# 2002_PIC32.net
KiCad netlist of a schematic drawn in Altium Designer
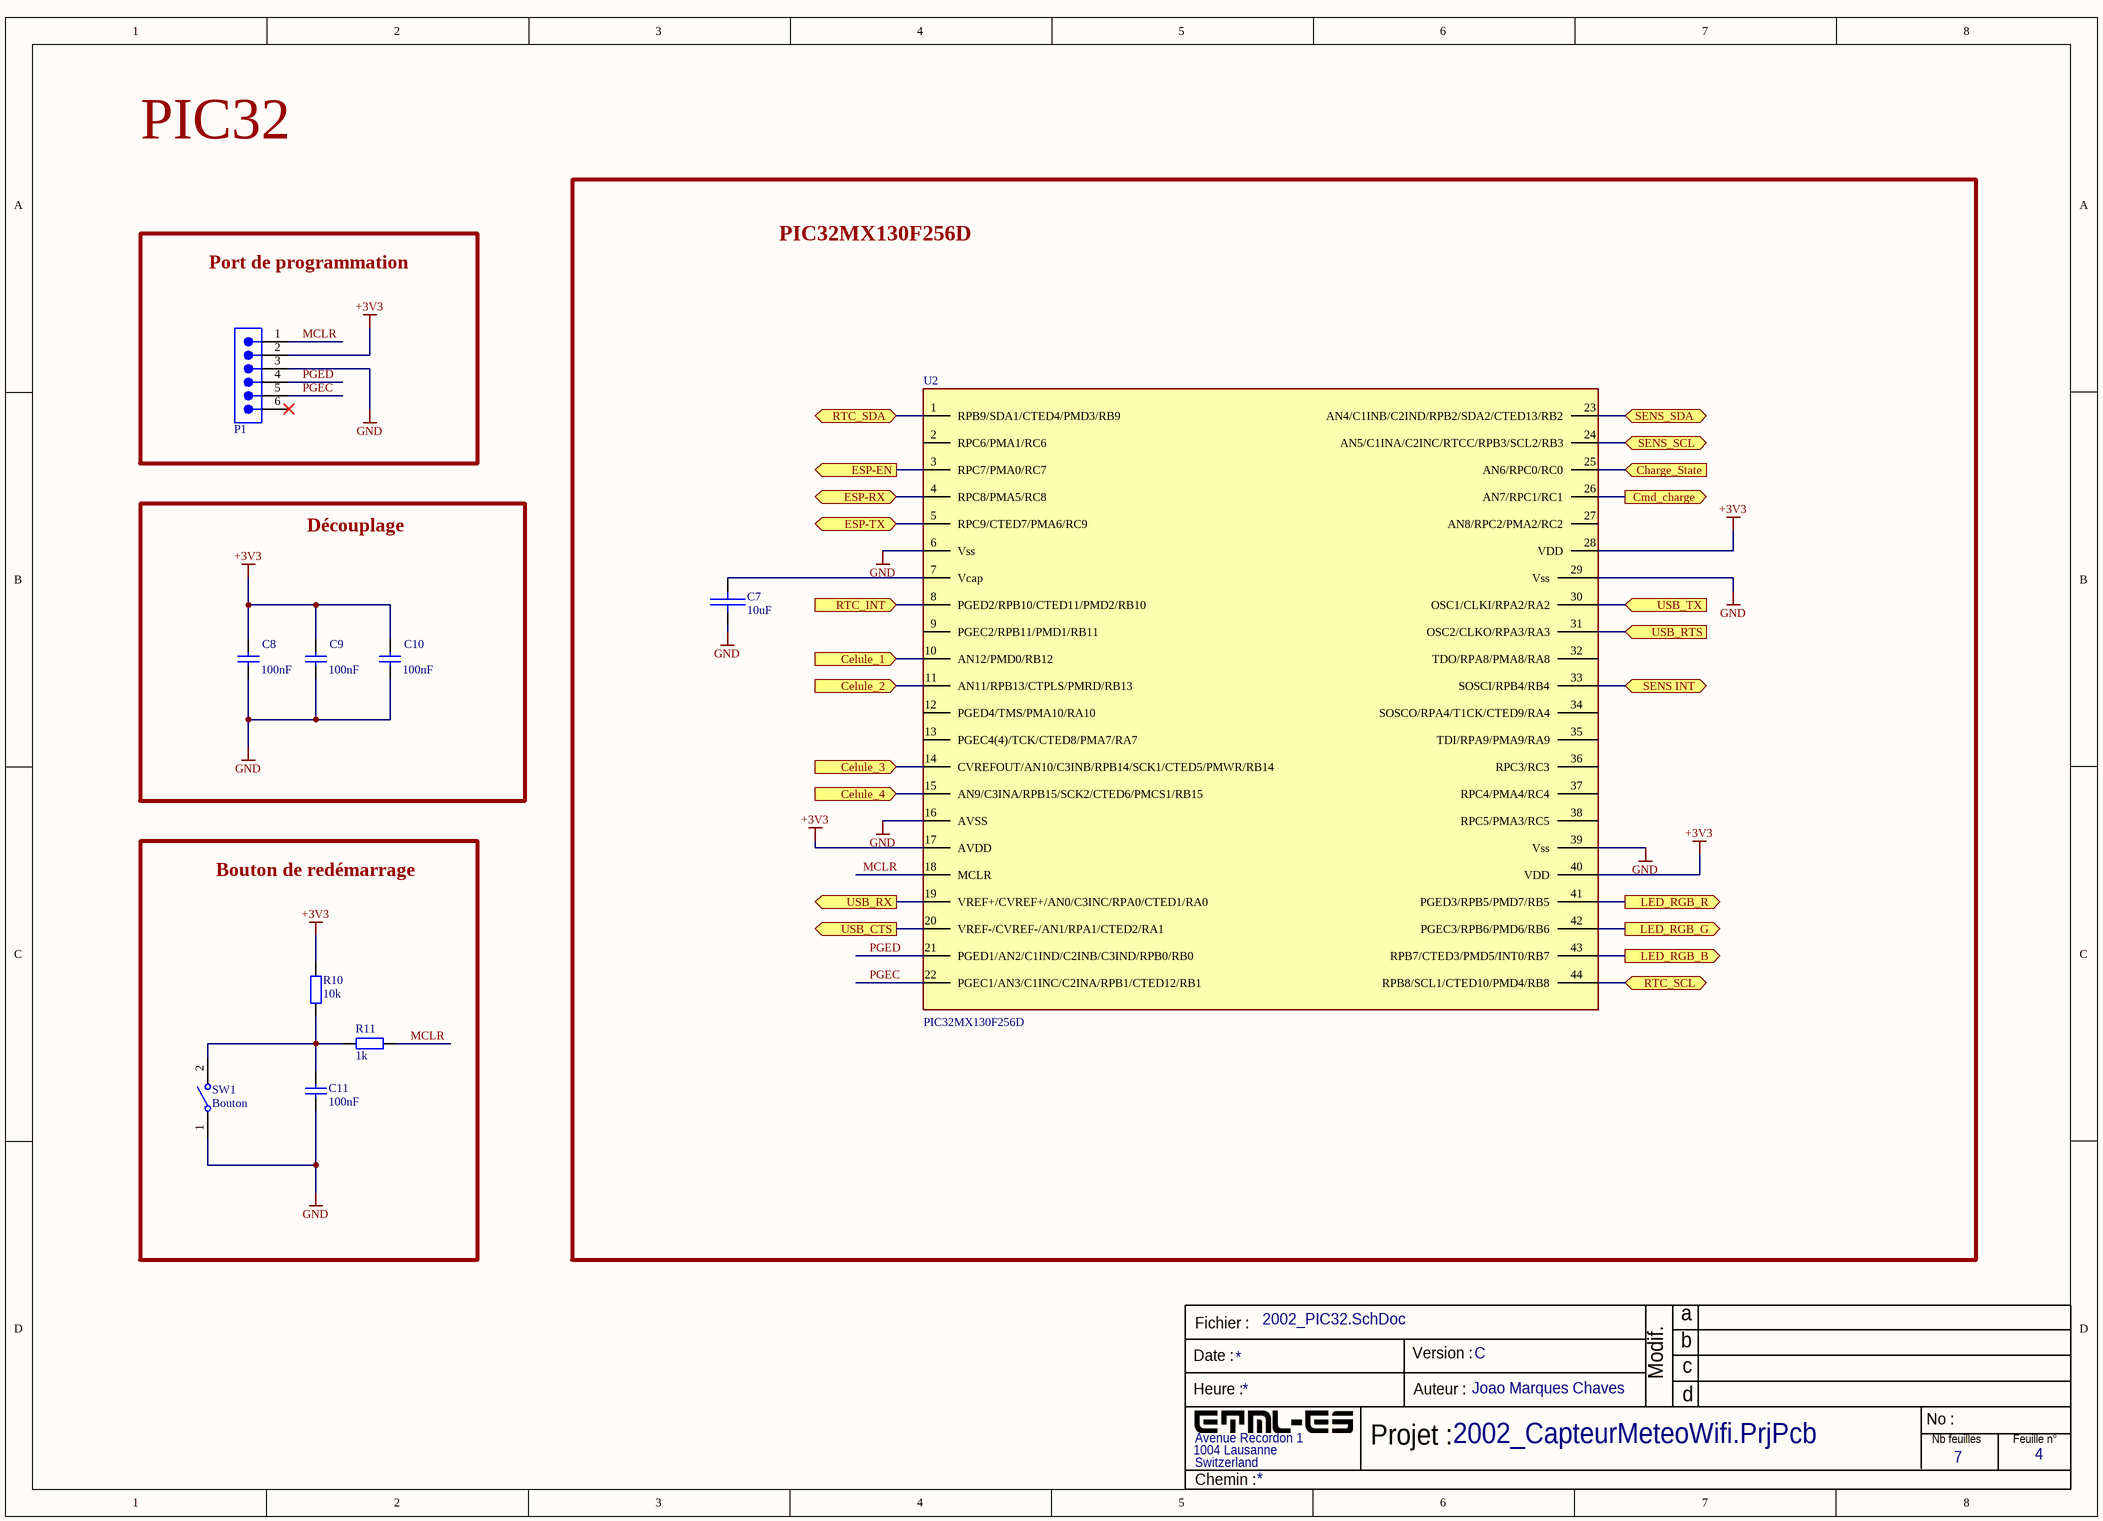
[diagram p0: 2002_PIC32.SchDoc]

(export (version "E")
  (design (tool "Eeschema 10.0.6"))
  (components
    (comp (ref "C7")
      (value "10uF")
      (footprint "0805")
      (description "0805 Condensator")
      (libsource (lib "2002_CapteurMeteoWifi") (part "Condensator"))
    )
    (comp (ref "C8")
      (value "100nF")
      (footprint "0805")
      (description "Capacitor smd")
      (fields
        (field (name "MANUFACTURER PART NUMBER") "885012207016")
        (field (name "MANUFACTURER") "Wurth Elektronik")
        (field (name "CAPACITANCE") "100nF")
      )
      (libsource (lib "WCAP-CSGP") (part "885012207016"))
    )
    (comp (ref "C9")
      (value "100nF")
      (footprint "0805")
      (description "Capacitor smd")
      (fields
        (field (name "MANUFACTURER PART NUMBER") "885012207016")
        (field (name "MANUFACTURER") "Wurth Elektronik")
        (field (name "CAPACITANCE") "100nF")
      )
      (libsource (lib "WCAP-CSGP") (part "885012207016"))
    )
    (comp (ref "C10")
      (value "100nF")
      (footprint "0805")
      (description "Capacitor smd")
      (fields
        (field (name "MANUFACTURER PART NUMBER") "885012207016")
        (field (name "MANUFACTURER") "Wurth Elektronik")
        (field (name "CAPACITANCE") "100nF")
      )
      (libsource (lib "WCAP-CSGP") (part "885012207016"))
    )
    (comp (ref "C11")
      (value "100nF")
      (footprint "0805")
      (description "Capacitor smd")
      (fields
        (field (name "MANUFACTURER PART NUMBER") "885012207016")
        (field (name "MANUFACTURER") "Wurth Elektronik")
        (field (name "CAPACITANCE") "100nF")
      )
      (libsource (lib "WCAP-CSGP") (part "885012207016"))
    )
    (comp (ref "P1")
      (value "6 Pin header")
      (footprint "conecteur 1x6")
      (description "WR-PHD Pin Header, THT, Vertical, pitch 2.54mm, 1 Row, 6P")
      (fields
        (field (name "MANUFACTURER PART NUMBER") "61300611121")
        (field (name "MANUFACTURER") "Wurth Elektronik")
      )
      (libsource (lib "WR-PHD") (part "61300611121"))
    )
    (comp (ref "R10")
      (value "10k")
      (footprint "0805")
      (description "SMD Resistor")
      (fields (field (name "RESISTANCE") "10k"))
      (libsource (lib "2312-MS-0805") (part "RES-0805"))
    )
    (comp (ref "R11")
      (value "1k")
      (footprint "0805")
      (description "SMD Resistor")
      (fields (field (name "RESISTANCE") "1k"))
      (libsource (lib "2312-MS-0805") (part "RES-0805"))
    )
    (comp (ref "SW1")
      (value "Bouton")
      (footprint "Switch")
      (description "Tactile Switches WS-TASV Tact Switch")
      (fields
        (field (name "MANUFACTURER PART NUMBER") "434121050836")
        (field (name "MANUFACTURER") "Wurth Elektronik")
      )
      (libsource (lib "WS-TASV") (part "434121050836"))
    )
    (comp (ref "U2")
      (value "PIC32MX130F256D")
      (footprint "PIC32MX130F256D-I/PT")
      (description "Integrated Circuit")
      (fields
        (field (name "MANUFACTURER_PART_NUMBER") "PIC32MX130F256D-50I/PT")
        (field (name "MOUSER PART NUMBER") "579-MX130F256D50IPT")
      )
      (libsource (lib "2002_CapteurMeteoWifi") (part "PIC32MX130F256B-I_SS"))
    )
  )
  (nets
    (net (code "1") (name "+3V3") (class "Default")
      (node (ref "C10") (pin "2") (pinfunction "2_2") (pintype "passive"))
      (node (ref "C8") (pin "2") (pinfunction "2_2") (pintype "passive"))
      (node (ref "C9") (pin "2") (pinfunction "2_2") (pintype "passive"))
      (node (ref "P1") (pin "2") (pinfunction "2_2") (pintype "passive"))
      (node (ref "R10") (pin "1") (pinfunction "1_1") (pintype "passive"))
      (node (ref "U2") (pin "17") (pinfunction "AVDD_17") (pintype "passive"))
      (node (ref "U2") (pin "28") (pinfunction "VDD_28") (pintype "passive"))
      (node (ref "U2") (pin "40") (pinfunction "VDD_40") (pintype "passive"))
    )
    (net (code "2") (name "/Celule_1") (class "Default")
      (node (ref "U2") (pin "10") (pinfunction "AN12/PMD0/RB12_10") (pintype "passive"))
    )
    (net (code "3") (name "/Celule_2") (class "Default")
      (node (ref "U2") (pin "11") (pinfunction "AN11/RPB13/CTPLS/PMRD/RB13_11") (pintype "passive"))
    )
    (net (code "4") (name "/Celule_3") (class "Default")
      (node (ref "U2") (pin "14") (pinfunction "CVREFOUT/AN10/C3INB/RPB14/SCK1/CTED5/PMWR/RB14_14") (pintype "passive"))
    )
    (net (code "5") (name "/Celule_4") (class "Default")
      (node (ref "U2") (pin "15") (pinfunction "AN9/C3INA/RPB15/SCK2/CTED6/PMCS1/RB15_15") (pintype "passive"))
    )
    (net (code "6") (name "/Charge_State") (class "Default")
      (node (ref "U2") (pin "25") (pinfunction "AN6/RPC0/RC0_25") (pintype "passive"))
    )
    (net (code "7") (name "/Cmd_charge") (class "Default")
      (node (ref "U2") (pin "26") (pinfunction "AN7/RPC1/RC1_26") (pintype "passive"))
    )
    (net (code "8") (name "/ESP-EN") (class "Default")
      (node (ref "U2") (pin "3") (pinfunction "RPC7/PMA0/RC7_3") (pintype "passive"))
    )
    (net (code "9") (name "/ESP-RX") (class "Default")
      (node (ref "U2") (pin "4") (pinfunction "RPC8/PMA5/RC8_4") (pintype "passive"))
    )
    (net (code "10") (name "/ESP-TX") (class "Default")
      (node (ref "U2") (pin "5") (pinfunction "RPC9/CTED7/PMA6/RC9_5") (pintype "passive"))
    )
    (net (code "11") (name "/LED_RGB_B") (class "Default")
      (node (ref "U2") (pin "43") (pinfunction "RPB7/CTED3/PMD5/INT0/RB7_43") (pintype "passive"))
    )
    (net (code "12") (name "/LED_RGB_G") (class "Default")
      (node (ref "U2") (pin "42") (pinfunction "PGEC3/RPB6/PMD6/RB6_42") (pintype "passive"))
    )
    (net (code "13") (name "/LED_RGB_R") (class "Default")
      (node (ref "U2") (pin "41") (pinfunction "PGED3/RPB5/PMD7/RB5_41") (pintype "passive"))
    )
    (net (code "14") (name "/MCLR") (class "Default")
      (node (ref "P1") (pin "1") (pinfunction "1_1") (pintype "passive"))
      (node (ref "R11") (pin "2") (pinfunction "2_2") (pintype "passive"))
      (node (ref "U2") (pin "18") (pinfunction "MCLR_18") (pintype "passive"))
    )
    (net (code "15") (name "/PGEC") (class "Default")
      (node (ref "P1") (pin "5") (pinfunction "5_5") (pintype "passive"))
      (node (ref "U2") (pin "22") (pinfunction "PGEC1/AN3/C1INC/C2INA/RPB1/CTED12/RB1_22") (pintype "passive"))
    )
    (net (code "16") (name "/PGED") (class "Default")
      (node (ref "P1") (pin "4") (pinfunction "4_4") (pintype "passive"))
      (node (ref "U2") (pin "21") (pinfunction "PGED1/AN2/C1IND/C2INB/C3IND/RPB0/RB0_21") (pintype "passive"))
    )
    (net (code "17") (name "/RTC_INT") (class "Default")
      (node (ref "U2") (pin "8") (pinfunction "PGED2/RPB10/CTED11/PMD2/RB10_8") (pintype "passive"))
    )
    (net (code "18") (name "/RTC_SCL") (class "Default")
      (node (ref "U2") (pin "44") (pinfunction "RPB8/SCL1/CTED10/PMD4/RB8_44") (pintype "passive"))
    )
    (net (code "19") (name "/RTC_SDA") (class "Default")
      (node (ref "U2") (pin "1") (pinfunction "RPB9/SDA1/CTED4/PMD3/RB9_1") (pintype "passive"))
    )
    (net (code "20") (name "/SENS INT") (class "Default")
      (node (ref "U2") (pin "33") (pinfunction "SOSCI/RPB4/RB4_33") (pintype "passive"))
    )
    (net (code "21") (name "/SENS_SCL") (class "Default")
      (node (ref "U2") (pin "24") (pinfunction "AN5/C1INA/C2INC/RTCC/RPB3/SCL2/RB3_24") (pintype "passive"))
    )
    (net (code "22") (name "/SENS_SDA") (class "Default")
      (node (ref "U2") (pin "23") (pinfunction "AN4/C1INB/C2IND/RPB2/SDA2/CTED13/RB2_23") (pintype "passive"))
    )
    (net (code "23") (name "/USB_CTS") (class "Default")
      (node (ref "U2") (pin "20") (pinfunction "VREF-/CVREF-/AN1/RPA1/CTED2/RA1_20") (pintype "passive"))
    )
    (net (code "24") (name "/USB_RTS") (class "Default")
      (node (ref "U2") (pin "31") (pinfunction "OSC2/CLKO/RPA3/RA3_31") (pintype "passive"))
    )
    (net (code "25") (name "/USB_RX") (class "Default")
      (node (ref "U2") (pin "19") (pinfunction "VREF+/CVREF+/AN0/C3INC/RPA0/CTED1/RA0_19") (pintype "passive"))
    )
    (net (code "26") (name "/USB_TX") (class "Default")
      (node (ref "U2") (pin "30") (pinfunction "OSC1/CLKI/RPA2/RA2_30") (pintype "passive"))
    )
    (net (code "27") (name "GND") (class "Default")
      (node (ref "C10") (pin "1") (pinfunction "1_1") (pintype "passive"))
      (node (ref "C11") (pin "2") (pinfunction "2_2") (pintype "passive"))
      (node (ref "C7") (pin "2") (pinfunction "2_2") (pintype "passive"))
      (node (ref "C8") (pin "1") (pinfunction "1_1") (pintype "passive"))
      (node (ref "C9") (pin "1") (pinfunction "1_1") (pintype "passive"))
      (node (ref "P1") (pin "3") (pinfunction "3_3") (pintype "passive"))
      (node (ref "SW1") (pin "1") (pinfunction "1_1") (pintype "passive"))
      (node (ref "U2") (pin "16") (pinfunction "AVSS_16") (pintype "passive"))
      (node (ref "U2") (pin "29") (pinfunction "Vss_29") (pintype "passive"))
      (node (ref "U2") (pin "39") (pinfunction "Vss_39") (pintype "passive"))
      (node (ref "U2") (pin "6") (pinfunction "Vss_6") (pintype "passive"))
    )
    (net (code "28") (name "Net-(C11-Pad1)") (class "Default")
      (node (ref "C11") (pin "1") (pinfunction "1_1") (pintype "passive"))
      (node (ref "R10") (pin "2") (pinfunction "2_2") (pintype "passive"))
      (node (ref "R11") (pin "1") (pinfunction "1_1") (pintype "passive"))
      (node (ref "SW1") (pin "2") (pinfunction "2_2") (pintype "passive"))
    )
    (net (code "29") (name "Net-(U2-Vcap)") (class "Default")
      (node (ref "C7") (pin "1") (pinfunction "1_1") (pintype "passive"))
      (node (ref "U2") (pin "7") (pinfunction "Vcap_7") (pintype "passive"))
    )
    (net (code "30") (name "unconnected-(P1-Pad6)") (class "Default")
      (node (ref "P1") (pin "6") (pinfunction "6_6") (pintype "passive+no_connect"))
    )
    (net (code "31") (name "unconnected-(U2-AN8{slash}RPC2{slash}PMA2{slash}RC2-Pad27)") (class "Default")
      (node (ref "U2") (pin "27") (pinfunction "AN8/RPC2/PMA2/RC2_27") (pintype "passive"))
    )
    (net (code "32") (name "unconnected-(U2-PGEC2{slash}RPB11{slash}PMD1{slash}RB11-Pad9)") (class "Default")
      (node (ref "U2") (pin "9") (pinfunction "PGEC2/RPB11/PMD1/RB11_9") (pintype "passive"))
    )
    (net (code "33") (name "unconnected-(U2-PGEC4(4){slash}TCK{slash}CTED8{slash}PMA7{slash}RA7-Pad13)") (class "Default")
      (node (ref "U2") (pin "13") (pinfunction "PGEC4(4)/TCK/CTED8/PMA7/RA7_13") (pintype "passive"))
    )
    (net (code "34") (name "unconnected-(U2-PGED4{slash}TMS{slash}PMA10{slash}RA10-Pad12)") (class "Default")
      (node (ref "U2") (pin "12") (pinfunction "PGED4/TMS/PMA10/RA10_12") (pintype "passive"))
    )
    (net (code "35") (name "unconnected-(U2-RPC3{slash}RC3-Pad36)") (class "Default")
      (node (ref "U2") (pin "36") (pinfunction "RPC3/RC3_36") (pintype "passive"))
    )
    (net (code "36") (name "unconnected-(U2-RPC4{slash}PMA4{slash}RC4-Pad37)") (class "Default")
      (node (ref "U2") (pin "37") (pinfunction "RPC4/PMA4/RC4_37") (pintype "passive"))
    )
    (net (code "37") (name "unconnected-(U2-RPC5{slash}PMA3{slash}RC5-Pad38)") (class "Default")
      (node (ref "U2") (pin "38") (pinfunction "RPC5/PMA3/RC5_38") (pintype "passive"))
    )
    (net (code "38") (name "unconnected-(U2-RPC6{slash}PMA1{slash}RC6-Pad2)") (class "Default")
      (node (ref "U2") (pin "2") (pinfunction "RPC6/PMA1/RC6_2") (pintype "passive"))
    )
    (net (code "39") (name "unconnected-(U2-SOSCO{slash}RPA4{slash}T1CK{slash}CTED9{slash}RA4-Pad34)") (class "Default")
      (node (ref "U2") (pin "34") (pinfunction "SOSCO/RPA4/T1CK/CTED9/RA4_34") (pintype "passive"))
    )
    (net (code "40") (name "unconnected-(U2-TDI{slash}RPA9{slash}PMA9{slash}RA9-Pad35)") (class "Default")
      (node (ref "U2") (pin "35") (pinfunction "TDI/RPA9/PMA9/RA9_35") (pintype "passive"))
    )
    (net (code "41") (name "unconnected-(U2-TDO{slash}RPA8{slash}PMA8{slash}RA8-Pad32)") (class "Default")
      (node (ref "U2") (pin "32") (pinfunction "TDO/RPA8/PMA8/RA8_32") (pintype "passive"))
    )
  )
)
